# Power.net
KiCad netlist of a schematic drawn in Altium Designer
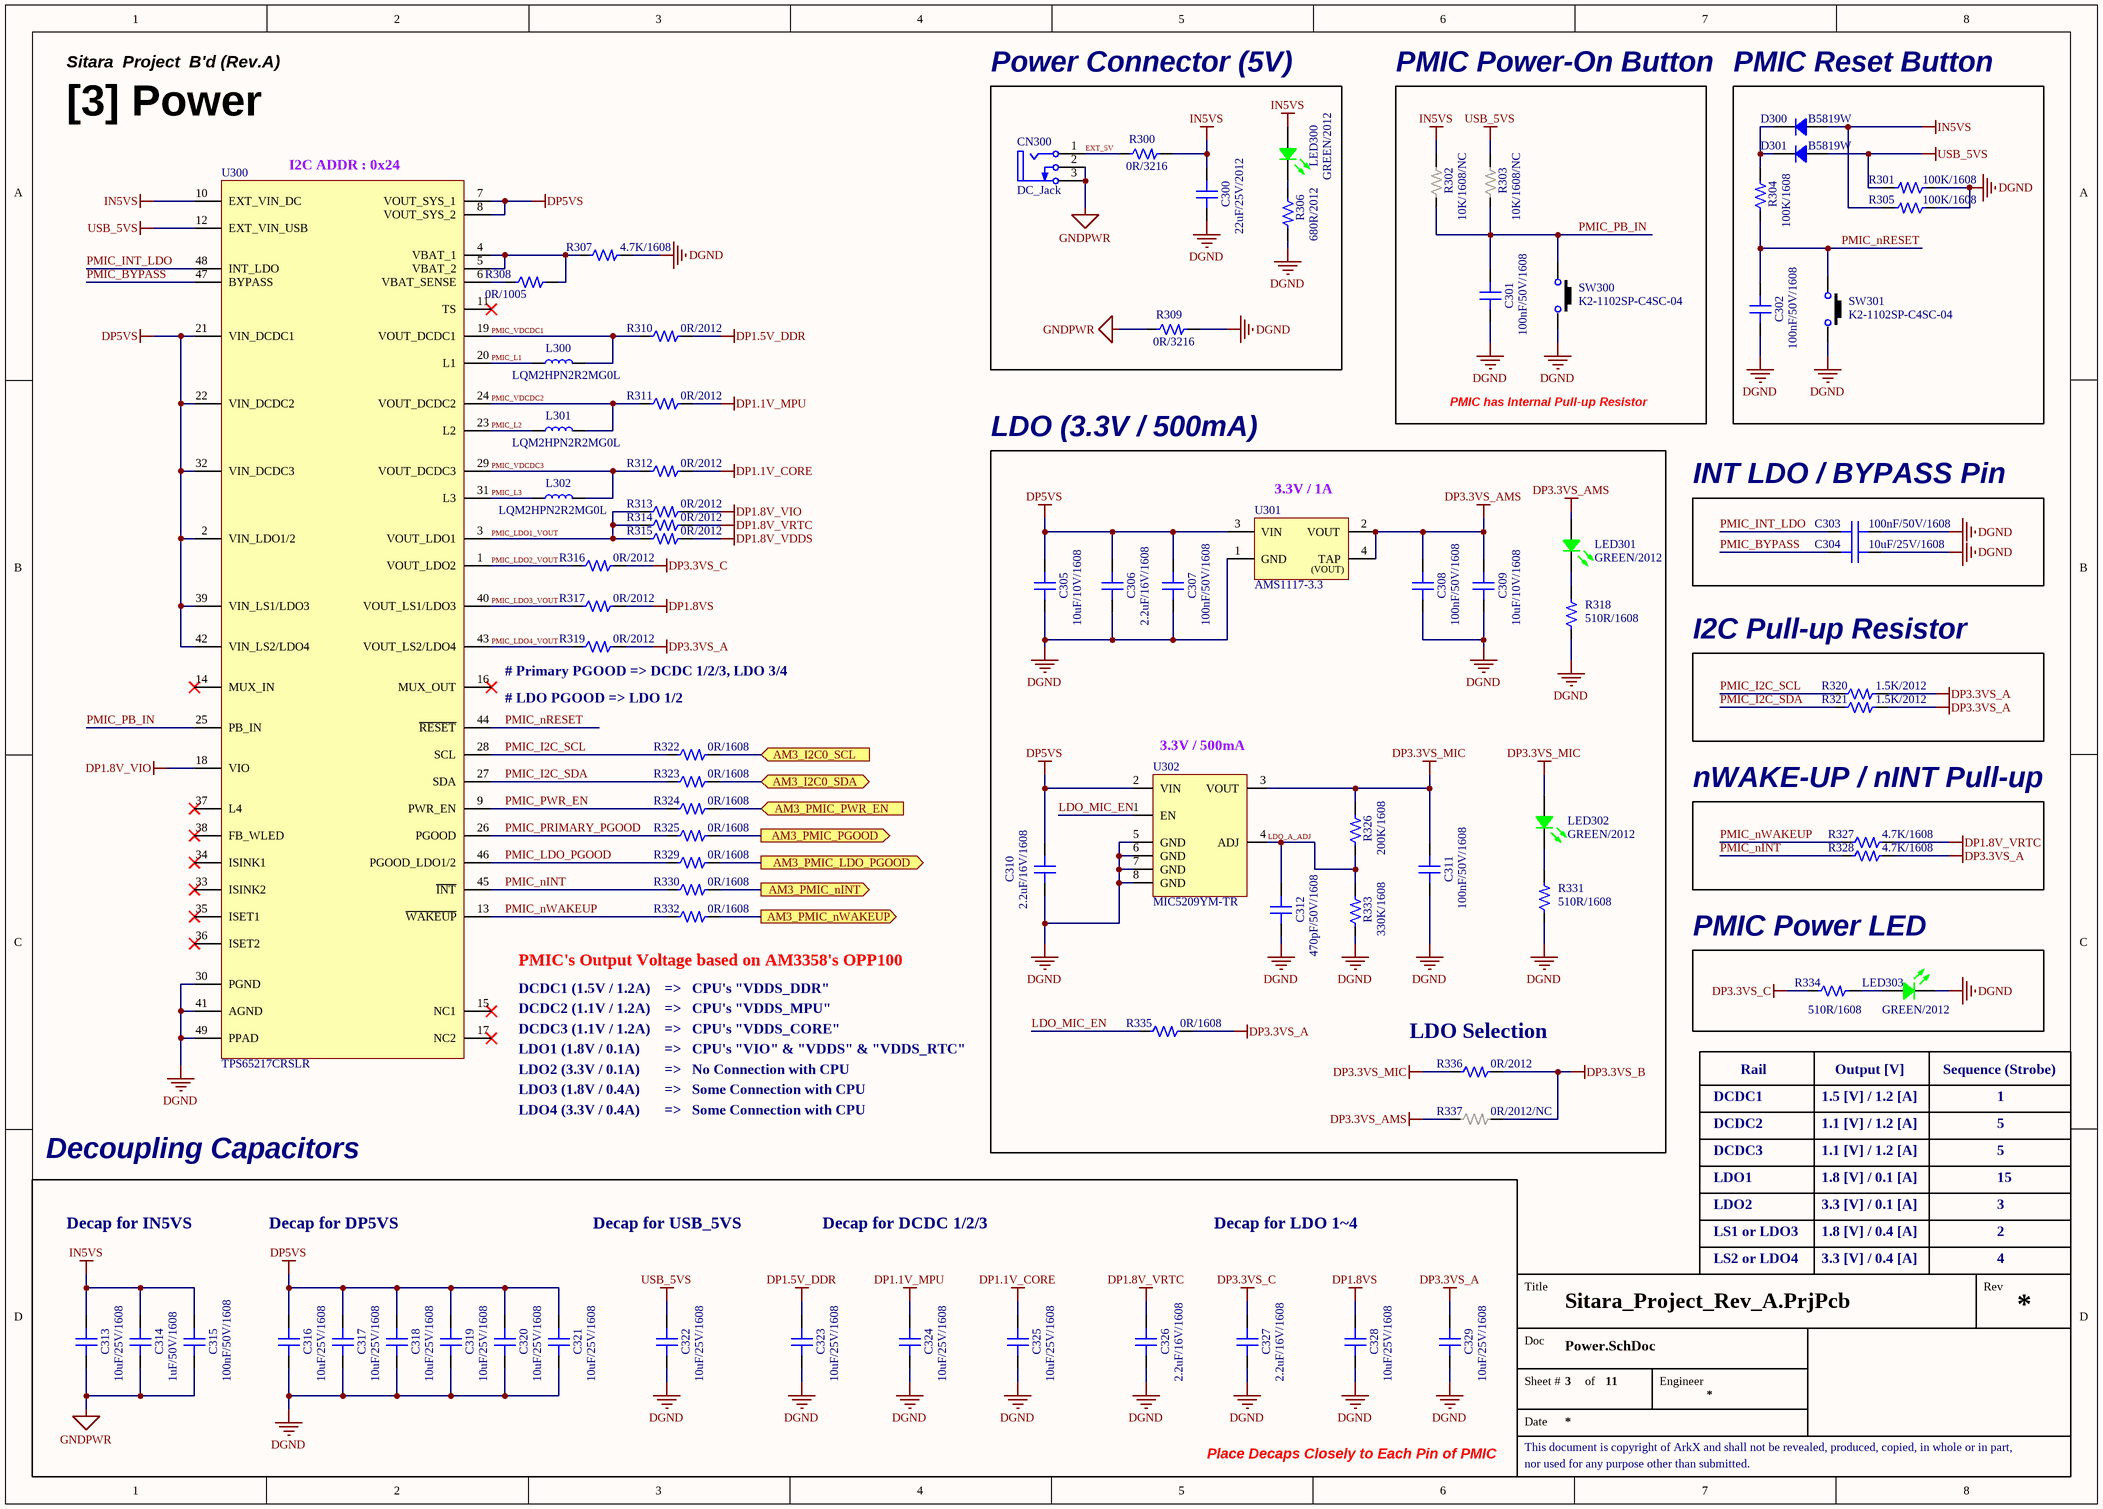
[diagram p0: Power.SchDoc]

(export (version "E")
  (design (tool "Eeschema 10.0.6"))
  (components
    (comp (ref "C300")
      (value "22uF/25V/2012")
      (footprint "CAP 2012 (0805_INCH)")
      (description "Ceramic CAP_22uF/25V/2012")
      (fields (field (name "LCSC PART #") "C45783"))
      (libsource (lib "Arkx") (part "CAP_22uF/25V/2012"))
    )
    (comp (ref "C301")
      (value "100nF/50V/1608")
      (footprint "CAP 1608 (0603_INCH)")
      (description "Ceramic CAP_100nF/50V/1608")
      (fields (field (name "LCSC PART #") "C14663"))
      (libsource (lib "Arkx") (part "CAP_100nF/50V/1608"))
    )
    (comp (ref "C302")
      (value "100nF/50V/1608")
      (footprint "CAP 1608 (0603_INCH)")
      (description "Ceramic CAP_100nF/50V/1608")
      (fields (field (name "LCSC PART #") "C14663"))
      (libsource (lib "Arkx") (part "CAP_100nF/50V/1608"))
    )
    (comp (ref "C303")
      (value "100nF/50V/1608")
      (footprint "CAP 1608 (0603_INCH)")
      (description "Ceramic CAP_100nF/50V/1608")
      (fields (field (name "LCSC PART #") "C14663"))
      (libsource (lib "Arkx") (part "CAP_100nF/50V/1608"))
    )
    (comp (ref "C304")
      (value "10uF/25V/1608")
      (footprint "CAP 1608 (0603_INCH)")
      (description "Ceramic CAP_10uF/25V/1608")
      (fields (field (name "LCSC PART #") "C96446"))
      (libsource (lib "Arkx") (part "CAP_10uF/25V/1608"))
    )
    (comp (ref "C305")
      (value "10uF/10V/1608")
      (footprint "CAP 1608 (0603_INCH)")
      (description "Ceramic CAP_10uF/10V/1608")
      (fields (field (name "LCSC PART #") "C19702"))
      (libsource (lib "Arkx") (part "CAP_10uF/10V/1608"))
    )
    (comp (ref "C306")
      (value "2.2uF/16V/1608")
      (footprint "CAP 1608 (0603_INCH)")
      (description "Ceramic CAP_2.2uF/16V/1608")
      (fields (field (name "LCSC PART #") "C23630"))
      (libsource (lib "Arkx") (part "CAP_2.2uF/16V/1608"))
    )
    (comp (ref "C307")
      (value "100nF/50V/1608")
      (footprint "CAP 1608 (0603_INCH)")
      (description "Ceramic CAP_100nF/50V/1608")
      (fields (field (name "LCSC PART #") "C14663"))
      (libsource (lib "Arkx") (part "CAP_100nF/50V/1608"))
    )
    (comp (ref "C308")
      (value "100nF/50V/1608")
      (footprint "CAP 1608 (0603_INCH)")
      (description "Ceramic CAP_100nF/50V/1608")
      (fields (field (name "LCSC PART #") "C14663"))
      (libsource (lib "Arkx") (part "CAP_100nF/50V/1608"))
    )
    (comp (ref "C309")
      (value "10uF/10V/1608")
      (footprint "CAP 1608 (0603_INCH)")
      (description "Ceramic CAP_10uF/10V/1608")
      (fields (field (name "LCSC PART #") "C19702"))
      (libsource (lib "Arkx") (part "CAP_10uF/10V/1608"))
    )
    (comp (ref "C310")
      (value "2.2uF/16V/1608")
      (footprint "CAP 1608 (0603_INCH)")
      (description "Ceramic CAP_2.2uF/16V/1608")
      (fields (field (name "LCSC PART #") "C23630"))
      (libsource (lib "Arkx") (part "CAP_2.2uF/16V/1608"))
    )
    (comp (ref "C311")
      (value "100nF/50V/1608")
      (footprint "CAP 1608 (0603_INCH)")
      (description "Ceramic CAP_100nF/50V/1608")
      (fields (field (name "LCSC PART #") "C14663"))
      (libsource (lib "Arkx") (part "CAP_100nF/50V/1608"))
    )
    (comp (ref "C312")
      (value "470pF/50V/1608")
      (footprint "CAP 1608 (0603_INCH)")
      (description "Ceramic CAP_470pF/50V/1608")
      (fields (field (name "LCSC PART #") "C1620"))
      (libsource (lib "Arkx") (part "CAP_470pF/50V/1608"))
    )
    (comp (ref "C313")
      (value "10uF/25V/1608")
      (footprint "CAP 1608 (0603_INCH)")
      (description "Ceramic CAP_10uF/25V/1608")
      (fields (field (name "LCSC PART #") "C96446"))
      (libsource (lib "Arkx") (part "CAP_10uF/25V/1608"))
    )
    (comp (ref "C314")
      (value "1uF/50V/1608")
      (footprint "CAP 1608 (0603_INCH)")
      (description "Ceramic CAP_1uF/50V/1608")
      (fields (field (name "LCSC PART #") "C15849"))
      (libsource (lib "Arkx") (part "CAP_1uF/50V/1608"))
    )
    (comp (ref "C315")
      (value "100nF/50V/1608")
      (footprint "CAP 1608 (0603_INCH)")
      (description "Ceramic CAP_100nF/50V/1608")
      (fields (field (name "LCSC PART #") "C14663"))
      (libsource (lib "Arkx") (part "CAP_100nF/50V/1608"))
    )
    (comp (ref "C316")
      (value "10uF/25V/1608")
      (footprint "CAP 1608 (0603_INCH)")
      (description "Ceramic CAP_10uF/25V/1608")
      (fields (field (name "LCSC PART #") "C96446"))
      (libsource (lib "Arkx") (part "CAP_10uF/25V/1608"))
    )
    (comp (ref "C317")
      (value "10uF/25V/1608")
      (footprint "CAP 1608 (0603_INCH)")
      (description "Ceramic CAP_10uF/25V/1608")
      (fields (field (name "LCSC PART #") "C96446"))
      (libsource (lib "Arkx") (part "CAP_10uF/25V/1608"))
    )
    (comp (ref "C318")
      (value "10uF/25V/1608")
      (footprint "CAP 1608 (0603_INCH)")
      (description "Ceramic CAP_10uF/25V/1608")
      (fields (field (name "LCSC PART #") "C96446"))
      (libsource (lib "Arkx") (part "CAP_10uF/25V/1608"))
    )
    (comp (ref "C319")
      (value "10uF/25V/1608")
      (footprint "CAP 1608 (0603_INCH)")
      (description "Ceramic CAP_10uF/25V/1608")
      (fields (field (name "LCSC PART #") "C96446"))
      (libsource (lib "Arkx") (part "CAP_10uF/25V/1608"))
    )
    (comp (ref "C320")
      (value "10uF/25V/1608")
      (footprint "CAP 1608 (0603_INCH)")
      (description "Ceramic CAP_10uF/25V/1608")
      (fields (field (name "LCSC PART #") "C96446"))
      (libsource (lib "Arkx") (part "CAP_10uF/25V/1608"))
    )
    (comp (ref "C321")
      (value "10uF/25V/1608")
      (footprint "CAP 1608 (0603_INCH)")
      (description "Ceramic CAP_10uF/25V/1608")
      (fields (field (name "LCSC PART #") "C96446"))
      (libsource (lib "Arkx") (part "CAP_10uF/25V/1608"))
    )
    (comp (ref "C322")
      (value "10uF/25V/1608")
      (footprint "CAP 1608 (0603_INCH)")
      (description "Ceramic CAP_10uF/25V/1608")
      (fields (field (name "LCSC PART #") "C96446"))
      (libsource (lib "Arkx") (part "CAP_10uF/25V/1608"))
    )
    (comp (ref "C323")
      (value "10uF/25V/1608")
      (footprint "CAP 1608 (0603_INCH)")
      (description "Ceramic CAP_10uF/25V/1608")
      (fields (field (name "LCSC PART #") "C96446"))
      (libsource (lib "Arkx") (part "CAP_10uF/25V/1608"))
    )
    (comp (ref "C324")
      (value "10uF/25V/1608")
      (footprint "CAP 1608 (0603_INCH)")
      (description "Ceramic CAP_10uF/25V/1608")
      (fields (field (name "LCSC PART #") "C96446"))
      (libsource (lib "Arkx") (part "CAP_10uF/25V/1608"))
    )
    (comp (ref "C325")
      (value "10uF/25V/1608")
      (footprint "CAP 1608 (0603_INCH)")
      (description "Ceramic CAP_10uF/25V/1608")
      (fields (field (name "LCSC PART #") "C96446"))
      (libsource (lib "Arkx") (part "CAP_10uF/25V/1608"))
    )
    (comp (ref "C326")
      (value "2.2uF/16V/1608")
      (footprint "CAP 1608 (0603_INCH)")
      (description "Ceramic CAP_2.2uF/16V/1608")
      (fields (field (name "LCSC PART #") "C23630"))
      (libsource (lib "Arkx") (part "CAP_2.2uF/16V/1608"))
    )
    (comp (ref "C327")
      (value "2.2uF/16V/1608")
      (footprint "CAP 1608 (0603_INCH)")
      (description "Ceramic CAP_2.2uF/16V/1608")
      (fields (field (name "LCSC PART #") "C23630"))
      (libsource (lib "Arkx") (part "CAP_2.2uF/16V/1608"))
    )
    (comp (ref "C328")
      (value "10uF/25V/1608")
      (footprint "CAP 1608 (0603_INCH)")
      (description "Ceramic CAP_10uF/25V/1608")
      (fields (field (name "LCSC PART #") "C96446"))
      (libsource (lib "Arkx") (part "CAP_10uF/25V/1608"))
    )
    (comp (ref "C329")
      (value "10uF/25V/1608")
      (footprint "CAP 1608 (0603_INCH)")
      (description "Ceramic CAP_10uF/25V/1608")
      (fields (field (name "LCSC PART #") "C96446"))
      (libsource (lib "Arkx") (part "CAP_10uF/25V/1608"))
    )
    (comp (ref "CN300")
      (value "DC_Jack")
      (footprint "CON_DC-JACK")
      (libsource (lib "Arkx") (part "CON_DC-Jack"))
    )
    (comp (ref "D300")
      (value "B5819W")
      (footprint "DIO_SOD-123")
      (description "40V 600mV@1A 1A SOD-123  Schottky Barrier Diodes (SBD) ROHS")
      (fields (field (name "LCSC PART #") "C8598"))
      (libsource (lib "Arkx") (part "DIO_B5819W"))
    )
    (comp (ref "D301")
      (value "B5819W")
      (footprint "DIO_SOD-123")
      (description "40V 600mV@1A 1A SOD-123  Schottky Barrier Diodes (SBD) ROHS")
      (fields (field (name "LCSC PART #") "C8598"))
      (libsource (lib "Arkx") (part "DIO_B5819W"))
    )
    (comp (ref "L300")
      (value "LQM2HPN2R2MG0L")
      (footprint "IND_LQM2HPN2R2MG0L")
      (description "2.2 µH Shielded Multilayer Inductor 1.3 A 100mOhm Max 1008 (2520 Metric)")
      (fields (field (name "LCSC PART #") "C86092"))
      (libsource (lib "Arkx") (part "IND_LQM2HPN2R2MG0L"))
    )
    (comp (ref "L301")
      (value "LQM2HPN2R2MG0L")
      (footprint "IND_LQM2HPN2R2MG0L")
      (description "2.2 µH Shielded Multilayer Inductor 1.3 A 100mOhm Max 1008 (2520 Metric)")
      (fields (field (name "LCSC PART #") "C86092"))
      (libsource (lib "Arkx") (part "IND_LQM2HPN2R2MG0L"))
    )
    (comp (ref "L302")
      (value "LQM2HPN2R2MG0L")
      (footprint "IND_LQM2HPN2R2MG0L")
      (description "2.2 µH Shielded Multilayer Inductor 1.3 A 100mOhm Max 1008 (2520 Metric)")
      (fields (field (name "LCSC PART #") "C86092"))
      (libsource (lib "Arkx") (part "IND_LQM2HPN2R2MG0L"))
    )
    (comp (ref "LED300")
      (value "GREEN/2012")
      (footprint "LED MHT170RGBCT (GREEN)")
      (fields (field (name "LCSC PART #") "C2962094"))
      (libsource (lib "Arkx") (part "LED_MHT170RGBCT(GREEN)"))
    )
    (comp (ref "LED301")
      (value "GREEN/2012")
      (footprint "LED MHT170RGBCT (GREEN)")
      (fields (field (name "LCSC PART #") "C2962094"))
      (libsource (lib "Arkx") (part "LED_MHT170RGBCT(GREEN)"))
    )
    (comp (ref "LED302")
      (value "GREEN/2012")
      (footprint "LED MHT170RGBCT (GREEN)")
      (fields (field (name "LCSC PART #") "C2962094"))
      (libsource (lib "Arkx") (part "LED_MHT170RGBCT(GREEN)"))
    )
    (comp (ref "LED303")
      (value "GREEN/2012")
      (footprint "LED MHT170RGBCT (GREEN)")
      (fields (field (name "LCSC PART #") "C2962094"))
      (libsource (lib "Arkx") (part "LED_MHT170RGBCT(GREEN)"))
    )
    (comp (ref "R300")
      (value "0R/3216")
      (footprint "RES 3216 (1206_inch)")
      (description "RES_0R/3216/0.25W")
      (fields (field (name "LCSC PART #") "C17888"))
      (libsource (lib "Arkx") (part "RES_0R/3216/0.25W"))
    )
    (comp (ref "R301")
      (value "100K/1608")
      (footprint "RES 1608 (0603_inch)")
      (description "RES_100K/1608/0.1W")
      (fields (field (name "LCSC PART #") "C25803"))
      (libsource (lib "Arkx") (part "RES_100K/1608/0.1W"))
    )
    (comp (ref "R302")
      (value "10K/1608/NC")
      (footprint "RES 1608 (0603_inch)/NC")
      (description "RES_10K/1608/0.1W")
      (libsource (lib "Arkx") (part "RES_NC_10K/1608/0.1W"))
    )
    (comp (ref "R303")
      (value "10K/1608/NC")
      (footprint "RES 1608 (0603_inch)/NC")
      (description "RES_10K/1608/0.1W")
      (libsource (lib "Arkx") (part "RES_NC_10K/1608/0.1W"))
    )
    (comp (ref "R304")
      (value "100K/1608")
      (footprint "RES 1608 (0603_inch)")
      (description "RES_100K/1608/0.1W")
      (fields (field (name "LCSC PART #") "C25803"))
      (libsource (lib "Arkx") (part "RES_100K/1608/0.1W"))
    )
    (comp (ref "R305")
      (value "100K/1608")
      (footprint "RES 1608 (0603_inch)")
      (description "RES_100K/1608/0.1W")
      (fields (field (name "LCSC PART #") "C25803"))
      (libsource (lib "Arkx") (part "RES_100K/1608/0.1W"))
    )
    (comp (ref "R306")
      (value "680R/2012")
      (footprint "RES 2012 (0805_inch)")
      (description "RES_680R/2012/0.125W")
      (fields (field (name "LCSC PART #") "C17798"))
      (libsource (lib "Arkx") (part "RES_680R/2012/0.125W"))
    )
    (comp (ref "R307")
      (value "4.7K/1608")
      (footprint "RES 1608 (0603_inch)")
      (description "RES_4.7K/1608/0.1W")
      (fields (field (name "LCSC PART #") "C23162"))
      (libsource (lib "Arkx") (part "RES_4.7K/1608/0.1W"))
    )
    (comp (ref "R308")
      (value "0R/1005")
      (footprint "RES 1005 (0402_inch)")
      (description "RES_0R/1005/62.5mW")
      (fields (field (name "LCSC PART #") "C17168"))
      (libsource (lib "Arkx") (part "RES_0R/1005/62.5mW"))
    )
    (comp (ref "R309")
      (value "0R/3216")
      (footprint "RES 3216 (1206_inch)")
      (description "RES_0R/3216/0.25W")
      (fields (field (name "LCSC PART #") "C17888"))
      (libsource (lib "Arkx") (part "RES_0R/3216/0.25W"))
    )
    (comp (ref "R310")
      (value "0R/2012")
      (footprint "RES 2012 (0805_inch)")
      (description "RES_0R/2012/0.125W")
      (fields (field (name "LCSC PART #") "C17477"))
      (libsource (lib "Arkx") (part "RES_0R/2012/0.125W"))
    )
    (comp (ref "R311")
      (value "0R/2012")
      (footprint "RES 2012 (0805_inch)")
      (description "RES_0R/2012/0.125W")
      (fields (field (name "LCSC PART #") "C17477"))
      (libsource (lib "Arkx") (part "RES_0R/2012/0.125W"))
    )
    (comp (ref "R312")
      (value "0R/2012")
      (footprint "RES 2012 (0805_inch)")
      (description "RES_0R/2012/0.125W")
      (fields (field (name "LCSC PART #") "C17477"))
      (libsource (lib "Arkx") (part "RES_0R/2012/0.125W"))
    )
    (comp (ref "R313")
      (value "0R/2012")
      (footprint "RES 2012 (0805_inch)")
      (description "RES_0R/2012/0.125W")
      (fields (field (name "LCSC PART #") "C17477"))
      (libsource (lib "Arkx") (part "RES_0R/2012/0.125W"))
    )
    (comp (ref "R314")
      (value "0R/2012")
      (footprint "RES 2012 (0805_inch)")
      (description "RES_0R/2012/0.125W")
      (fields (field (name "LCSC PART #") "C17477"))
      (libsource (lib "Arkx") (part "RES_0R/2012/0.125W"))
    )
    (comp (ref "R315")
      (value "0R/2012")
      (footprint "RES 2012 (0805_inch)")
      (description "RES_0R/2012/0.125W")
      (fields (field (name "LCSC PART #") "C17477"))
      (libsource (lib "Arkx") (part "RES_0R/2012/0.125W"))
    )
    (comp (ref "R316")
      (value "0R/2012")
      (footprint "RES 2012 (0805_inch)")
      (description "RES_0R/2012/0.125W")
      (fields (field (name "LCSC PART #") "C17477"))
      (libsource (lib "Arkx") (part "RES_0R/2012/0.125W"))
    )
    (comp (ref "R317")
      (value "0R/2012")
      (footprint "RES 2012 (0805_inch)")
      (description "RES_0R/2012/0.125W")
      (fields (field (name "LCSC PART #") "C17477"))
      (libsource (lib "Arkx") (part "RES_0R/2012/0.125W"))
    )
    (comp (ref "R318")
      (value "510R/1608")
      (footprint "RES 1608 (0603_inch)")
      (description "RES_510R/1608/0.1W")
      (fields (field (name "LCSC PART #") "C23193"))
      (libsource (lib "Arkx") (part "RES_510R/1608/0.1W"))
    )
    (comp (ref "R319")
      (value "0R/2012")
      (footprint "RES 2012 (0805_inch)")
      (description "RES_0R/2012/0.125W")
      (fields (field (name "LCSC PART #") "C17477"))
      (libsource (lib "Arkx") (part "RES_0R/2012/0.125W"))
    )
    (comp (ref "R320")
      (value "1.5K/2012")
      (footprint "RES 2012 (0805_inch)")
      (description "RES_1.5K/2012/0.125W")
      (fields (field (name "LCSC PART #") "C4310"))
      (libsource (lib "Arkx") (part "RES_1.5K/2012/0.125W"))
    )
    (comp (ref "R321")
      (value "1.5K/2012")
      (footprint "RES 2012 (0805_inch)")
      (description "RES_1.5K/2012/0.125W")
      (fields (field (name "LCSC PART #") "C4310"))
      (libsource (lib "Arkx") (part "RES_1.5K/2012/0.125W"))
    )
    (comp (ref "R322")
      (value "0R/1608")
      (footprint "RES 1608 (0603_inch)")
      (description "RES_0R/1608/0.1W")
      (fields (field (name "LCSC PART #") "C21189"))
      (libsource (lib "Arkx") (part "RES_0R/1608/0.1W"))
    )
    (comp (ref "R323")
      (value "0R/1608")
      (footprint "RES 1608 (0603_inch)")
      (description "RES_0R/1608/0.1W")
      (fields (field (name "LCSC PART #") "C21189"))
      (libsource (lib "Arkx") (part "RES_0R/1608/0.1W"))
    )
    (comp (ref "R324")
      (value "0R/1608")
      (footprint "RES 1608 (0603_inch)")
      (description "RES_0R/1608/0.1W")
      (fields (field (name "LCSC PART #") "C21189"))
      (libsource (lib "Arkx") (part "RES_0R/1608/0.1W"))
    )
    (comp (ref "R325")
      (value "0R/1608")
      (footprint "RES 1608 (0603_inch)")
      (description "RES_0R/1608/0.1W")
      (fields (field (name "LCSC PART #") "C21189"))
      (libsource (lib "Arkx") (part "RES_0R/1608/0.1W"))
    )
    (comp (ref "R326")
      (value "200K/1608")
      (footprint "RES 1608 (0603_inch)")
      (description "RES_200K/1608/0.1W")
      (fields (field (name "LCSC PART #") "C25811"))
      (libsource (lib "Arkx") (part "RES_200K/1608/0.1W"))
    )
    (comp (ref "R327")
      (value "4.7K/1608")
      (footprint "RES 1608 (0603_inch)")
      (description "RES_4.7K/1608/0.1W")
      (fields (field (name "LCSC PART #") "C23162"))
      (libsource (lib "Arkx") (part "RES_4.7K/1608/0.1W"))
    )
    (comp (ref "R328")
      (value "4.7K/1608")
      (footprint "RES 1608 (0603_inch)")
      (description "RES_4.7K/1608/0.1W")
      (fields (field (name "LCSC PART #") "C23162"))
      (libsource (lib "Arkx") (part "RES_4.7K/1608/0.1W"))
    )
    (comp (ref "R329")
      (value "0R/1608")
      (footprint "RES 1608 (0603_inch)")
      (description "RES_0R/1608/0.1W")
      (fields (field (name "LCSC PART #") "C21189"))
      (libsource (lib "Arkx") (part "RES_0R/1608/0.1W"))
    )
    (comp (ref "R330")
      (value "0R/1608")
      (footprint "RES 1608 (0603_inch)")
      (description "RES_0R/1608/0.1W")
      (fields (field (name "LCSC PART #") "C21189"))
      (libsource (lib "Arkx") (part "RES_0R/1608/0.1W"))
    )
    (comp (ref "R331")
      (value "510R/1608")
      (footprint "RES 1608 (0603_inch)")
      (description "RES_510R/1608/0.1W")
      (fields (field (name "LCSC PART #") "C23193"))
      (libsource (lib "Arkx") (part "RES_510R/1608/0.1W"))
    )
    (comp (ref "R332")
      (value "0R/1608")
      (footprint "RES 1608 (0603_inch)")
      (description "RES_0R/1608/0.1W")
      (fields (field (name "LCSC PART #") "C21189"))
      (libsource (lib "Arkx") (part "RES_0R/1608/0.1W"))
    )
    (comp (ref "R333")
      (value "330K/1608")
      (footprint "RES 1608 (0603_inch)")
      (description "RES_330K/1608/0.1W")
      (fields (field (name "LCSC PART #") "C23137"))
      (libsource (lib "Arkx") (part "RES_330K/1608/0.1W"))
    )
    (comp (ref "R334")
      (value "510R/1608")
      (footprint "RES 1608 (0603_inch)")
      (description "RES_510R/1608/0.1W")
      (fields (field (name "LCSC PART #") "C23193"))
      (libsource (lib "Arkx") (part "RES_510R/1608/0.1W"))
    )
    (comp (ref "R335")
      (value "0R/1608")
      (footprint "RES 1608 (0603_inch)")
      (description "RES_0R/1608/0.1W")
      (fields (field (name "LCSC PART #") "C21189"))
      (libsource (lib "Arkx") (part "RES_0R/1608/0.1W"))
    )
    (comp (ref "R336")
      (value "0R/2012")
      (footprint "RES 2012 (0805_inch)")
      (description "RES_0R/2012/0.125W")
      (fields (field (name "LCSC PART #") "C17477"))
      (libsource (lib "Arkx") (part "RES_0R/2012/0.125W"))
    )
    (comp (ref "R337")
      (value "0R/2012/NC")
      (footprint "RES 2012 (0805_INCH)/NC")
      (description "0R/2012/0.125W/NC")
      (libsource (lib "Arkx") (part "RES_NC_0R/2012/0.125W"))
    )
    (comp (ref "SW300")
      (value "K2-1102SP-C4SC-04")
      (footprint "SW K2-1102SP-C4SC-04")
      (fields (field (name "LCSC PART #") "C127509"))
      (libsource (lib "Arkx") (part "SW_K2-1102SP-C4SC-04(2P)"))
    )
    (comp (ref "SW301")
      (value "K2-1102SP-C4SC-04")
      (footprint "SW K2-1102SP-C4SC-04")
      (fields (field (name "LCSC PART #") "C127509"))
      (libsource (lib "Arkx") (part "SW_K2-1102SP-C4SC-04(2P)"))
    )
    (comp (ref "U300")
      (value "TPS65217CRSLR")
      (footprint "IC_VQFN-48(6x6)")
      (fields (field (name "LCSC PART #") "C116081"))
      (libsource (lib "Arkx") (part "IC_PMIC_TPS65217CRSLR"))
    )
    (comp (ref "U301")
      (value "AMS1117-3.3")
      (footprint "SOT 223-3 (DIODES INCORPORATED)")
      (fields (field (name "LCSC PART #") "C6186"))
      (libsource (lib "Arkx") (part "IC_REG_AMS1117-3.3"))
    )
    (comp (ref "U302")
      (value "MIC5209YM-TR")
      (footprint "IC_SOIC-8 (4.90x3.90mm)")
      (description "Linear Voltage Regulator IC Positive Adjustable 1 Output 500mA 8-SOIC")
      (fields (field (name "LCSC PART #") "C461593"))
      (libsource (lib "Arkx") (part "IC_REG_MIC5209YM-TR"))
    )
  )
  (nets
    (net (code "1") (name "/AM3_I2C0_SCL") (class "Default")
      (node (ref "R322") (pin "2") (pinfunction "2_2") (pintype "passive"))
    )
    (net (code "2") (name "/AM3_I2C0_SDA") (class "Default")
      (node (ref "R323") (pin "2") (pinfunction "2_2") (pintype "passive"))
    )
    (net (code "3") (name "/AM3_PMIC_LDO_PGOOD") (class "Default")
      (node (ref "R329") (pin "2") (pinfunction "2_2") (pintype "passive"))
    )
    (net (code "4") (name "/AM3_PMIC_PGOOD") (class "Default")
      (node (ref "R325") (pin "2") (pinfunction "2_2") (pintype "passive"))
    )
    (net (code "5") (name "/AM3_PMIC_PWR_EN") (class "Default")
      (node (ref "R324") (pin "2") (pinfunction "2_2") (pintype "passive"))
    )
    (net (code "6") (name "/AM3_PMIC_nINT") (class "Default")
      (node (ref "R330") (pin "2") (pinfunction "2_2") (pintype "passive"))
    )
    (net (code "7") (name "/AM3_PMIC_nWAKEUP") (class "Default")
      (node (ref "R332") (pin "2") (pinfunction "2_2") (pintype "passive"))
    )
    (net (code "8") (name "/EXT_5V") (class "Default")
      (node (ref "CN300") (pin "1") (pinfunction "VCC_1") (pintype "power_in"))
      (node (ref "R300") (pin "1") (pinfunction "1_1") (pintype "passive"))
    )
    (net (code "9") (name "/LDO_A_ADJ") (class "Default")
      (node (ref "C312") (pin "2") (pinfunction "2_2") (pintype "passive"))
      (node (ref "R326") (pin "1") (pinfunction "1_1") (pintype "passive"))
      (node (ref "R333") (pin "2") (pinfunction "2_2") (pintype "passive"))
      (node (ref "U302") (pin "4") (pinfunction "ADJ_4") (pintype "passive"))
    )
    (net (code "10") (name "/LDO_MIC_EN") (class "Default")
      (node (ref "R335") (pin "1") (pinfunction "1_1") (pintype "passive"))
      (node (ref "U302") (pin "1") (pinfunction "EN_1") (pintype "passive"))
    )
    (net (code "11") (name "/PMIC_BYPASS") (class "Default")
      (node (ref "C304") (pin "2") (pinfunction "2_2") (pintype "passive"))
      (node (ref "U300") (pin "47") (pinfunction "BYPASS_47") (pintype "passive"))
    )
    (net (code "12") (name "/PMIC_I2C_SCL") (class "Default")
      (node (ref "R320") (pin "1") (pinfunction "1_1") (pintype "passive"))
      (node (ref "R322") (pin "1") (pinfunction "1_1") (pintype "passive"))
      (node (ref "U300") (pin "28") (pinfunction "SCL_28") (pintype "passive"))
    )
    (net (code "13") (name "/PMIC_I2C_SDA") (class "Default")
      (node (ref "R321") (pin "1") (pinfunction "1_1") (pintype "passive"))
      (node (ref "R323") (pin "1") (pinfunction "1_1") (pintype "passive"))
      (node (ref "U300") (pin "27") (pinfunction "SDA_27") (pintype "passive"))
    )
    (net (code "14") (name "/PMIC_INT_LDO") (class "Default")
      (node (ref "C303") (pin "2") (pinfunction "2_2") (pintype "passive"))
      (node (ref "U300") (pin "48") (pinfunction "INT_LDO_48") (pintype "passive"))
    )
    (net (code "15") (name "/PMIC_L1") (class "Default")
      (node (ref "L300") (pin "1") (pinfunction "1_1") (pintype "passive"))
      (node (ref "U300") (pin "20") (pinfunction "L1_20") (pintype "passive"))
    )
    (net (code "16") (name "/PMIC_L2") (class "Default")
      (node (ref "L301") (pin "1") (pinfunction "1_1") (pintype "passive"))
      (node (ref "U300") (pin "23") (pinfunction "L2_23") (pintype "passive"))
    )
    (net (code "17") (name "/PMIC_L3") (class "Default")
      (node (ref "L302") (pin "1") (pinfunction "1_1") (pintype "passive"))
      (node (ref "U300") (pin "31") (pinfunction "L3_31") (pintype "passive"))
    )
    (net (code "18") (name "/PMIC_LDO1_VOUT") (class "Default")
      (node (ref "R313") (pin "1") (pinfunction "1_1") (pintype "passive"))
      (node (ref "R314") (pin "1") (pinfunction "1_1") (pintype "passive"))
      (node (ref "R315") (pin "1") (pinfunction "1_1") (pintype "passive"))
      (node (ref "U300") (pin "3") (pinfunction "VOUT_LDO1_3") (pintype "passive"))
    )
    (net (code "19") (name "/PMIC_LDO2_VOUT") (class "Default")
      (node (ref "R316") (pin "1") (pinfunction "1_1") (pintype "passive"))
      (node (ref "U300") (pin "1") (pinfunction "VOUT_LDO2_1") (pintype "passive"))
    )
    (net (code "20") (name "/PMIC_LDO3_VOUT") (class "Default")
      (node (ref "R317") (pin "1") (pinfunction "1_1") (pintype "passive"))
      (node (ref "U300") (pin "40") (pinfunction "VOUT_LS1/LDO3_40") (pintype "passive"))
    )
    (net (code "21") (name "/PMIC_LDO4_VOUT") (class "Default")
      (node (ref "R319") (pin "1") (pinfunction "1_1") (pintype "passive"))
      (node (ref "U300") (pin "43") (pinfunction "VOUT_LS2/LDO4_43") (pintype "passive"))
    )
    (net (code "22") (name "/PMIC_LDO_PGOOD") (class "Default")
      (node (ref "R329") (pin "1") (pinfunction "1_1") (pintype "passive"))
      (node (ref "U300") (pin "46") (pinfunction "PGOOD_LDO1/2_46") (pintype "passive"))
    )
    (net (code "23") (name "/PMIC_PB_IN") (class "Default")
      (node (ref "C301") (pin "2") (pinfunction "2_2") (pintype "passive"))
      (node (ref "R302") (pin "1") (pinfunction "1_1") (pintype "passive"))
      (node (ref "R303") (pin "1") (pinfunction "1_1") (pintype "passive"))
      (node (ref "SW300") (pin "1") (pinfunction "1_1") (pintype "passive"))
      (node (ref "U300") (pin "25") (pinfunction "PB_IN_25") (pintype "passive"))
    )
    (net (code "24") (name "/PMIC_PRIMARY_PGOOD") (class "Default")
      (node (ref "R325") (pin "1") (pinfunction "1_1") (pintype "passive"))
      (node (ref "U300") (pin "26") (pinfunction "PGOOD_26") (pintype "passive"))
    )
    (net (code "25") (name "/PMIC_PWR_EN") (class "Default")
      (node (ref "R324") (pin "1") (pinfunction "1_1") (pintype "passive"))
      (node (ref "U300") (pin "9") (pinfunction "PWR_EN_9") (pintype "passive"))
    )
    (net (code "26") (name "/PMIC_VDCDC1") (class "Default")
      (node (ref "L300") (pin "2") (pinfunction "2_2") (pintype "passive"))
      (node (ref "R310") (pin "1") (pinfunction "1_1") (pintype "passive"))
      (node (ref "U300") (pin "19") (pinfunction "VOUT_DCDC1_19") (pintype "passive"))
    )
    (net (code "27") (name "/PMIC_VDCDC2") (class "Default")
      (node (ref "L301") (pin "2") (pinfunction "2_2") (pintype "passive"))
      (node (ref "R311") (pin "1") (pinfunction "1_1") (pintype "passive"))
      (node (ref "U300") (pin "24") (pinfunction "VOUT_DCDC2_24") (pintype "passive"))
    )
    (net (code "28") (name "/PMIC_VDCDC3") (class "Default")
      (node (ref "L302") (pin "2") (pinfunction "2_2") (pintype "passive"))
      (node (ref "R312") (pin "1") (pinfunction "1_1") (pintype "passive"))
      (node (ref "U300") (pin "29") (pinfunction "VOUT_DCDC3_29") (pintype "passive"))
    )
    (net (code "29") (name "/PMIC_nINT") (class "Default")
      (node (ref "R328") (pin "1") (pinfunction "1_1") (pintype "passive"))
      (node (ref "R330") (pin "1") (pinfunction "1_1") (pintype "passive"))
      (node (ref "U300") (pin "45") (pinfunction "~{INT}_45") (pintype "passive"))
    )
    (net (code "30") (name "/PMIC_nRESET") (class "Default")
      (node (ref "C302") (pin "2") (pinfunction "2_2") (pintype "passive"))
      (node (ref "R304") (pin "1") (pinfunction "1_1") (pintype "passive"))
      (node (ref "SW301") (pin "1") (pinfunction "1_1") (pintype "passive"))
      (node (ref "U300") (pin "44") (pinfunction "~{RESET}_44") (pintype "passive"))
    )
    (net (code "31") (name "/PMIC_nWAKEUP") (class "Default")
      (node (ref "R327") (pin "1") (pinfunction "1_1") (pintype "passive"))
      (node (ref "R332") (pin "1") (pinfunction "1_1") (pintype "passive"))
      (node (ref "U300") (pin "13") (pinfunction "~{WAKEUP}_13") (pintype "passive"))
    )
    (net (code "32") (name "DGND") (class "Default")
      (node (ref "C300") (pin "1") (pinfunction "1_1") (pintype "passive"))
      (node (ref "C301") (pin "1") (pinfunction "1_1") (pintype "passive"))
      (node (ref "C302") (pin "1") (pinfunction "1_1") (pintype "passive"))
      (node (ref "C303") (pin "1") (pinfunction "1_1") (pintype "passive"))
      (node (ref "C304") (pin "1") (pinfunction "1_1") (pintype "passive"))
      (node (ref "C305") (pin "1") (pinfunction "1_1") (pintype "passive"))
      (node (ref "C306") (pin "1") (pinfunction "1_1") (pintype "passive"))
      (node (ref "C307") (pin "1") (pinfunction "1_1") (pintype "passive"))
      (node (ref "C308") (pin "1") (pinfunction "1_1") (pintype "passive"))
      (node (ref "C309") (pin "1") (pinfunction "1_1") (pintype "passive"))
      (node (ref "C310") (pin "1") (pinfunction "1_1") (pintype "passive"))
      (node (ref "C311") (pin "1") (pinfunction "1_1") (pintype "passive"))
      (node (ref "C312") (pin "1") (pinfunction "1_1") (pintype "passive"))
      (node (ref "C316") (pin "1") (pinfunction "1_1") (pintype "passive"))
      (node (ref "C317") (pin "1") (pinfunction "1_1") (pintype "passive"))
      (node (ref "C318") (pin "1") (pinfunction "1_1") (pintype "passive"))
      (node (ref "C319") (pin "1") (pinfunction "1_1") (pintype "passive"))
      (node (ref "C320") (pin "1") (pinfunction "1_1") (pintype "passive"))
      (node (ref "C321") (pin "1") (pinfunction "1_1") (pintype "passive"))
      (node (ref "C322") (pin "1") (pinfunction "1_1") (pintype "passive"))
      (node (ref "C323") (pin "1") (pinfunction "1_1") (pintype "passive"))
      (node (ref "C324") (pin "1") (pinfunction "1_1") (pintype "passive"))
      (node (ref "C325") (pin "1") (pinfunction "1_1") (pintype "passive"))
      (node (ref "C326") (pin "1") (pinfunction "1_1") (pintype "passive"))
      (node (ref "C327") (pin "1") (pinfunction "1_1") (pintype "passive"))
      (node (ref "C328") (pin "1") (pinfunction "1_1") (pintype "passive"))
      (node (ref "C329") (pin "1") (pinfunction "1_1") (pintype "passive"))
      (node (ref "LED303") (pin "2") (pinfunction "GREEN_2") (pintype "passive"))
      (node (ref "R301") (pin "1") (pinfunction "1_1") (pintype "passive"))
      (node (ref "R305") (pin "1") (pinfunction "1_1") (pintype "passive"))
      (node (ref "R306") (pin "2") (pinfunction "2_2") (pintype "passive"))
      (node (ref "R307") (pin "2") (pinfunction "2_2") (pintype "passive"))
      (node (ref "R309") (pin "2") (pinfunction "2_2") (pintype "passive"))
      (node (ref "R318") (pin "1") (pinfunction "1_1") (pintype "passive"))
      (node (ref "R331") (pin "1") (pinfunction "1_1") (pintype "passive"))
      (node (ref "R333") (pin "1") (pinfunction "1_1") (pintype "passive"))
      (node (ref "SW300") (pin "3") (pinfunction "3_3") (pintype "passive"))
      (node (ref "SW301") (pin "3") (pinfunction "3_3") (pintype "passive"))
      (node (ref "U300") (pin "30") (pinfunction "PGND_30") (pintype "passive"))
      (node (ref "U300") (pin "41") (pinfunction "AGND_41") (pintype "passive"))
      (node (ref "U300") (pin "49") (pinfunction "PPAD_49") (pintype "passive"))
      (node (ref "U301") (pin "1") (pinfunction "GND_1") (pintype "passive"))
      (node (ref "U302") (pin "5") (pinfunction "GND_5") (pintype "power_in"))
      (node (ref "U302") (pin "6") (pinfunction "GND_6") (pintype "power_in"))
      (node (ref "U302") (pin "7") (pinfunction "GND_7") (pintype "power_in"))
      (node (ref "U302") (pin "8") (pinfunction "GND_8") (pintype "power_in"))
    )
    (net (code "33") (name "DP1.1V_CORE") (class "Default")
      (node (ref "C325") (pin "2") (pinfunction "2_2") (pintype "passive"))
      (node (ref "R312") (pin "2") (pinfunction "2_2") (pintype "passive"))
    )
    (net (code "34") (name "DP1.1V_MPU") (class "Default")
      (node (ref "C324") (pin "2") (pinfunction "2_2") (pintype "passive"))
      (node (ref "R311") (pin "2") (pinfunction "2_2") (pintype "passive"))
    )
    (net (code "35") (name "DP1.5V_DDR") (class "Default")
      (node (ref "C323") (pin "2") (pinfunction "2_2") (pintype "passive"))
      (node (ref "R310") (pin "2") (pinfunction "2_2") (pintype "passive"))
    )
    (net (code "36") (name "DP1.8VS") (class "Default")
      (node (ref "C328") (pin "2") (pinfunction "2_2") (pintype "passive"))
      (node (ref "R317") (pin "2") (pinfunction "2_2") (pintype "passive"))
    )
    (net (code "37") (name "DP1.8V_VDDS") (class "Default")
      (node (ref "R315") (pin "2") (pinfunction "2_2") (pintype "passive"))
    )
    (net (code "38") (name "DP1.8V_VIO") (class "Default")
      (node (ref "R313") (pin "2") (pinfunction "2_2") (pintype "passive"))
      (node (ref "U300") (pin "18") (pinfunction "VIO_18") (pintype "passive"))
    )
    (net (code "39") (name "DP1.8V_VRTC") (class "Default")
      (node (ref "C326") (pin "2") (pinfunction "2_2") (pintype "passive"))
      (node (ref "R314") (pin "2") (pinfunction "2_2") (pintype "passive"))
      (node (ref "R327") (pin "2") (pinfunction "2_2") (pintype "passive"))
    )
    (net (code "40") (name "DP3.3VS_A") (class "Default")
      (node (ref "C329") (pin "2") (pinfunction "2_2") (pintype "passive"))
      (node (ref "R319") (pin "2") (pinfunction "2_2") (pintype "passive"))
      (node (ref "R320") (pin "2") (pinfunction "2_2") (pintype "passive"))
      (node (ref "R321") (pin "2") (pinfunction "2_2") (pintype "passive"))
      (node (ref "R328") (pin "2") (pinfunction "2_2") (pintype "passive"))
      (node (ref "R335") (pin "2") (pinfunction "2_2") (pintype "passive"))
    )
    (net (code "41") (name "DP3.3VS_AMS") (class "Default")
      (node (ref "C308") (pin "2") (pinfunction "2_2") (pintype "passive"))
      (node (ref "C309") (pin "2") (pinfunction "2_2") (pintype "passive"))
      (node (ref "LED301") (pin "4") (pinfunction "Common_Anode_4") (pintype "passive"))
      (node (ref "R337") (pin "1") (pinfunction "1_1") (pintype "passive"))
      (node (ref "U301") (pin "2") (pinfunction "VOUT_2") (pintype "passive"))
      (node (ref "U301") (pin "4") (pinfunction "TAP_4") (pintype "passive"))
    )
    (net (code "42") (name "DP3.3VS_B") (class "Default")
      (node (ref "R336") (pin "2") (pinfunction "2_2") (pintype "passive"))
      (node (ref "R337") (pin "2") (pinfunction "2_2") (pintype "passive"))
    )
    (net (code "43") (name "DP3.3VS_C") (class "Default")
      (node (ref "C327") (pin "2") (pinfunction "2_2") (pintype "passive"))
      (node (ref "R316") (pin "2") (pinfunction "2_2") (pintype "passive"))
      (node (ref "R334") (pin "1") (pinfunction "1_1") (pintype "passive"))
    )
    (net (code "44") (name "DP3.3VS_MIC") (class "Default")
      (node (ref "C311") (pin "2") (pinfunction "2_2") (pintype "passive"))
      (node (ref "LED302") (pin "4") (pinfunction "Common_Anode_4") (pintype "passive"))
      (node (ref "R326") (pin "2") (pinfunction "2_2") (pintype "passive"))
      (node (ref "R336") (pin "1") (pinfunction "1_1") (pintype "passive"))
      (node (ref "U302") (pin "3") (pinfunction "VOUT_3") (pintype "power_in"))
    )
    (net (code "45") (name "DP5VS") (class "Default")
      (node (ref "C305") (pin "2") (pinfunction "2_2") (pintype "passive"))
      (node (ref "C306") (pin "2") (pinfunction "2_2") (pintype "passive"))
      (node (ref "C307") (pin "2") (pinfunction "2_2") (pintype "passive"))
      (node (ref "C310") (pin "2") (pinfunction "2_2") (pintype "passive"))
      (node (ref "C316") (pin "2") (pinfunction "2_2") (pintype "passive"))
      (node (ref "C317") (pin "2") (pinfunction "2_2") (pintype "passive"))
      (node (ref "C318") (pin "2") (pinfunction "2_2") (pintype "passive"))
      (node (ref "C319") (pin "2") (pinfunction "2_2") (pintype "passive"))
      (node (ref "C320") (pin "2") (pinfunction "2_2") (pintype "passive"))
      (node (ref "C321") (pin "2") (pinfunction "2_2") (pintype "passive"))
      (node (ref "U300") (pin "2") (pinfunction "VIN_LDO1/2_2") (pintype "passive"))
      (node (ref "U300") (pin "21") (pinfunction "VIN_DCDC1_21") (pintype "passive"))
      (node (ref "U300") (pin "22") (pinfunction "VIN_DCDC2_22") (pintype "passive"))
      (node (ref "U300") (pin "32") (pinfunction "VIN_DCDC3_32") (pintype "passive"))
      (node (ref "U300") (pin "39") (pinfunction "VIN_LS1/LDO3_39") (pintype "passive"))
      (node (ref "U300") (pin "42") (pinfunction "VIN_LS2/LDO4_42") (pintype "passive"))
      (node (ref "U300") (pin "7") (pinfunction "VOUT_SYS_1_7") (pintype "passive"))
      (node (ref "U300") (pin "8") (pinfunction "VOUT_SYS_2_8") (pintype "passive"))
      (node (ref "U301") (pin "3") (pinfunction "VIN_3") (pintype "passive"))
      (node (ref "U302") (pin "2") (pinfunction "VIN_2") (pintype "power_in"))
    )
    (net (code "46") (name "GNDPWR") (class "Default")
      (node (ref "C313") (pin "1") (pinfunction "1_1") (pintype "passive"))
      (node (ref "C314") (pin "1") (pinfunction "1_1") (pintype "passive"))
      (node (ref "C315") (pin "1") (pinfunction "1_1") (pintype "passive"))
      (node (ref "CN300") (pin "2") (pinfunction "GND_2") (pintype "power_in"))
      (node (ref "CN300") (pin "3") (pinfunction "GND_3") (pintype "power_in"))
      (node (ref "R309") (pin "1") (pinfunction "1_1") (pintype "passive"))
    )
    (net (code "47") (name "IN5VS") (class "Default")
      (node (ref "C300") (pin "2") (pinfunction "2_2") (pintype "passive"))
      (node (ref "C313") (pin "2") (pinfunction "2_2") (pintype "passive"))
      (node (ref "C314") (pin "2") (pinfunction "2_2") (pintype "passive"))
      (node (ref "C315") (pin "2") (pinfunction "2_2") (pintype "passive"))
      (node (ref "D300") (pin "1") (pinfunction "1_1") (pintype "passive"))
      (node (ref "LED300") (pin "4") (pinfunction "Common_Anode_4") (pintype "passive"))
      (node (ref "R300") (pin "2") (pinfunction "2_2") (pintype "passive"))
      (node (ref "R302") (pin "2") (pinfunction "2_2") (pintype "passive"))
      (node (ref "R305") (pin "2") (pinfunction "2_2") (pintype "passive"))
      (node (ref "U300") (pin "10") (pinfunction "EXT_VIN_DC_10") (pintype "passive"))
    )
    (net (code "48") (name "Net-(D300-Pad2)") (class "Default")
      (node (ref "D300") (pin "2") (pinfunction "2_2") (pintype "passive"))
      (node (ref "D301") (pin "2") (pinfunction "2_2") (pintype "passive"))
      (node (ref "R304") (pin "2") (pinfunction "2_2") (pintype "passive"))
    )
    (net (code "49") (name "Net-(LED300-GREEN)") (class "Default")
      (node (ref "LED300") (pin "2") (pinfunction "GREEN_2") (pintype "passive"))
      (node (ref "R306") (pin "1") (pinfunction "1_1") (pintype "passive"))
    )
    (net (code "50") (name "Net-(LED301-GREEN)") (class "Default")
      (node (ref "LED301") (pin "2") (pinfunction "GREEN_2") (pintype "passive"))
      (node (ref "R318") (pin "2") (pinfunction "2_2") (pintype "passive"))
    )
    (net (code "51") (name "Net-(LED302-GREEN)") (class "Default")
      (node (ref "LED302") (pin "2") (pinfunction "GREEN_2") (pintype "passive"))
      (node (ref "R331") (pin "2") (pinfunction "2_2") (pintype "passive"))
    )
    (net (code "52") (name "Net-(LED303-Common_Anode)") (class "Default")
      (node (ref "LED303") (pin "4") (pinfunction "Common_Anode_4") (pintype "passive"))
      (node (ref "R334") (pin "2") (pinfunction "2_2") (pintype "passive"))
    )
    (net (code "53") (name "Net-(U300-VBAT_1)") (class "Default")
      (node (ref "R307") (pin "1") (pinfunction "1_1") (pintype "passive"))
      (node (ref "R308") (pin "2") (pinfunction "2_2") (pintype "passive"))
      (node (ref "U300") (pin "4") (pinfunction "VBAT_1_4") (pintype "passive"))
      (node (ref "U300") (pin "5") (pinfunction "VBAT_2_5") (pintype "passive"))
    )
    (net (code "54") (name "Net-(U300-VBAT_SENSE)") (class "Default")
      (node (ref "R308") (pin "1") (pinfunction "1_1") (pintype "passive"))
      (node (ref "U300") (pin "6") (pinfunction "VBAT_SENSE_6") (pintype "passive"))
    )
    (net (code "55") (name "USB_5VS") (class "Default")
      (node (ref "C322") (pin "2") (pinfunction "2_2") (pintype "passive"))
      (node (ref "D301") (pin "1") (pinfunction "1_1") (pintype "passive"))
      (node (ref "R301") (pin "2") (pinfunction "2_2") (pintype "passive"))
      (node (ref "R303") (pin "2") (pinfunction "2_2") (pintype "passive"))
      (node (ref "U300") (pin "12") (pinfunction "EXT_VIN_USB_12") (pintype "passive"))
    )
    (net (code "56") (name "unconnected-(U300-FB_WLED-Pad38)") (class "Default")
      (node (ref "U300") (pin "38") (pinfunction "FB_WLED_38") (pintype "passive+no_connect"))
    )
    (net (code "57") (name "unconnected-(U300-ISET1-Pad35)") (class "Default")
      (node (ref "U300") (pin "35") (pinfunction "ISET1_35") (pintype "passive+no_connect"))
    )
    (net (code "58") (name "unconnected-(U300-ISET2-Pad36)") (class "Default")
      (node (ref "U300") (pin "36") (pinfunction "ISET2_36") (pintype "passive+no_connect"))
    )
    (net (code "59") (name "unconnected-(U300-ISINK1-Pad34)") (class "Default")
      (node (ref "U300") (pin "34") (pinfunction "ISINK1_34") (pintype "passive+no_connect"))
    )
    (net (code "60") (name "unconnected-(U300-ISINK2-Pad33)") (class "Default")
      (node (ref "U300") (pin "33") (pinfunction "ISINK2_33") (pintype "passive+no_connect"))
    )
    (net (code "61") (name "unconnected-(U300-L4-Pad37)") (class "Default")
      (node (ref "U300") (pin "37") (pinfunction "L4_37") (pintype "passive+no_connect"))
    )
    (net (code "62") (name "unconnected-(U300-MUX_IN-Pad14)") (class "Default")
      (node (ref "U300") (pin "14") (pinfunction "MUX_IN_14") (pintype "passive+no_connect"))
    )
    (net (code "63") (name "unconnected-(U300-MUX_OUT-Pad16)") (class "Default")
      (node (ref "U300") (pin "16") (pinfunction "MUX_OUT_16") (pintype "passive+no_connect"))
    )
    (net (code "64") (name "unconnected-(U300-NC1-Pad15)") (class "Default")
      (node (ref "U300") (pin "15") (pinfunction "NC1_15") (pintype "passive+no_connect"))
    )
    (net (code "65") (name "unconnected-(U300-NC2-Pad17)") (class "Default")
      (node (ref "U300") (pin "17") (pinfunction "NC2_17") (pintype "passive+no_connect"))
    )
    (net (code "66") (name "unconnected-(U300-TS-Pad11)") (class "Default")
      (node (ref "U300") (pin "11") (pinfunction "TS_11") (pintype "passive+no_connect"))
    )
  )
)
